# ElectronBoardMKII.net
KiCad netlist of a schematic drawn in EAGLE
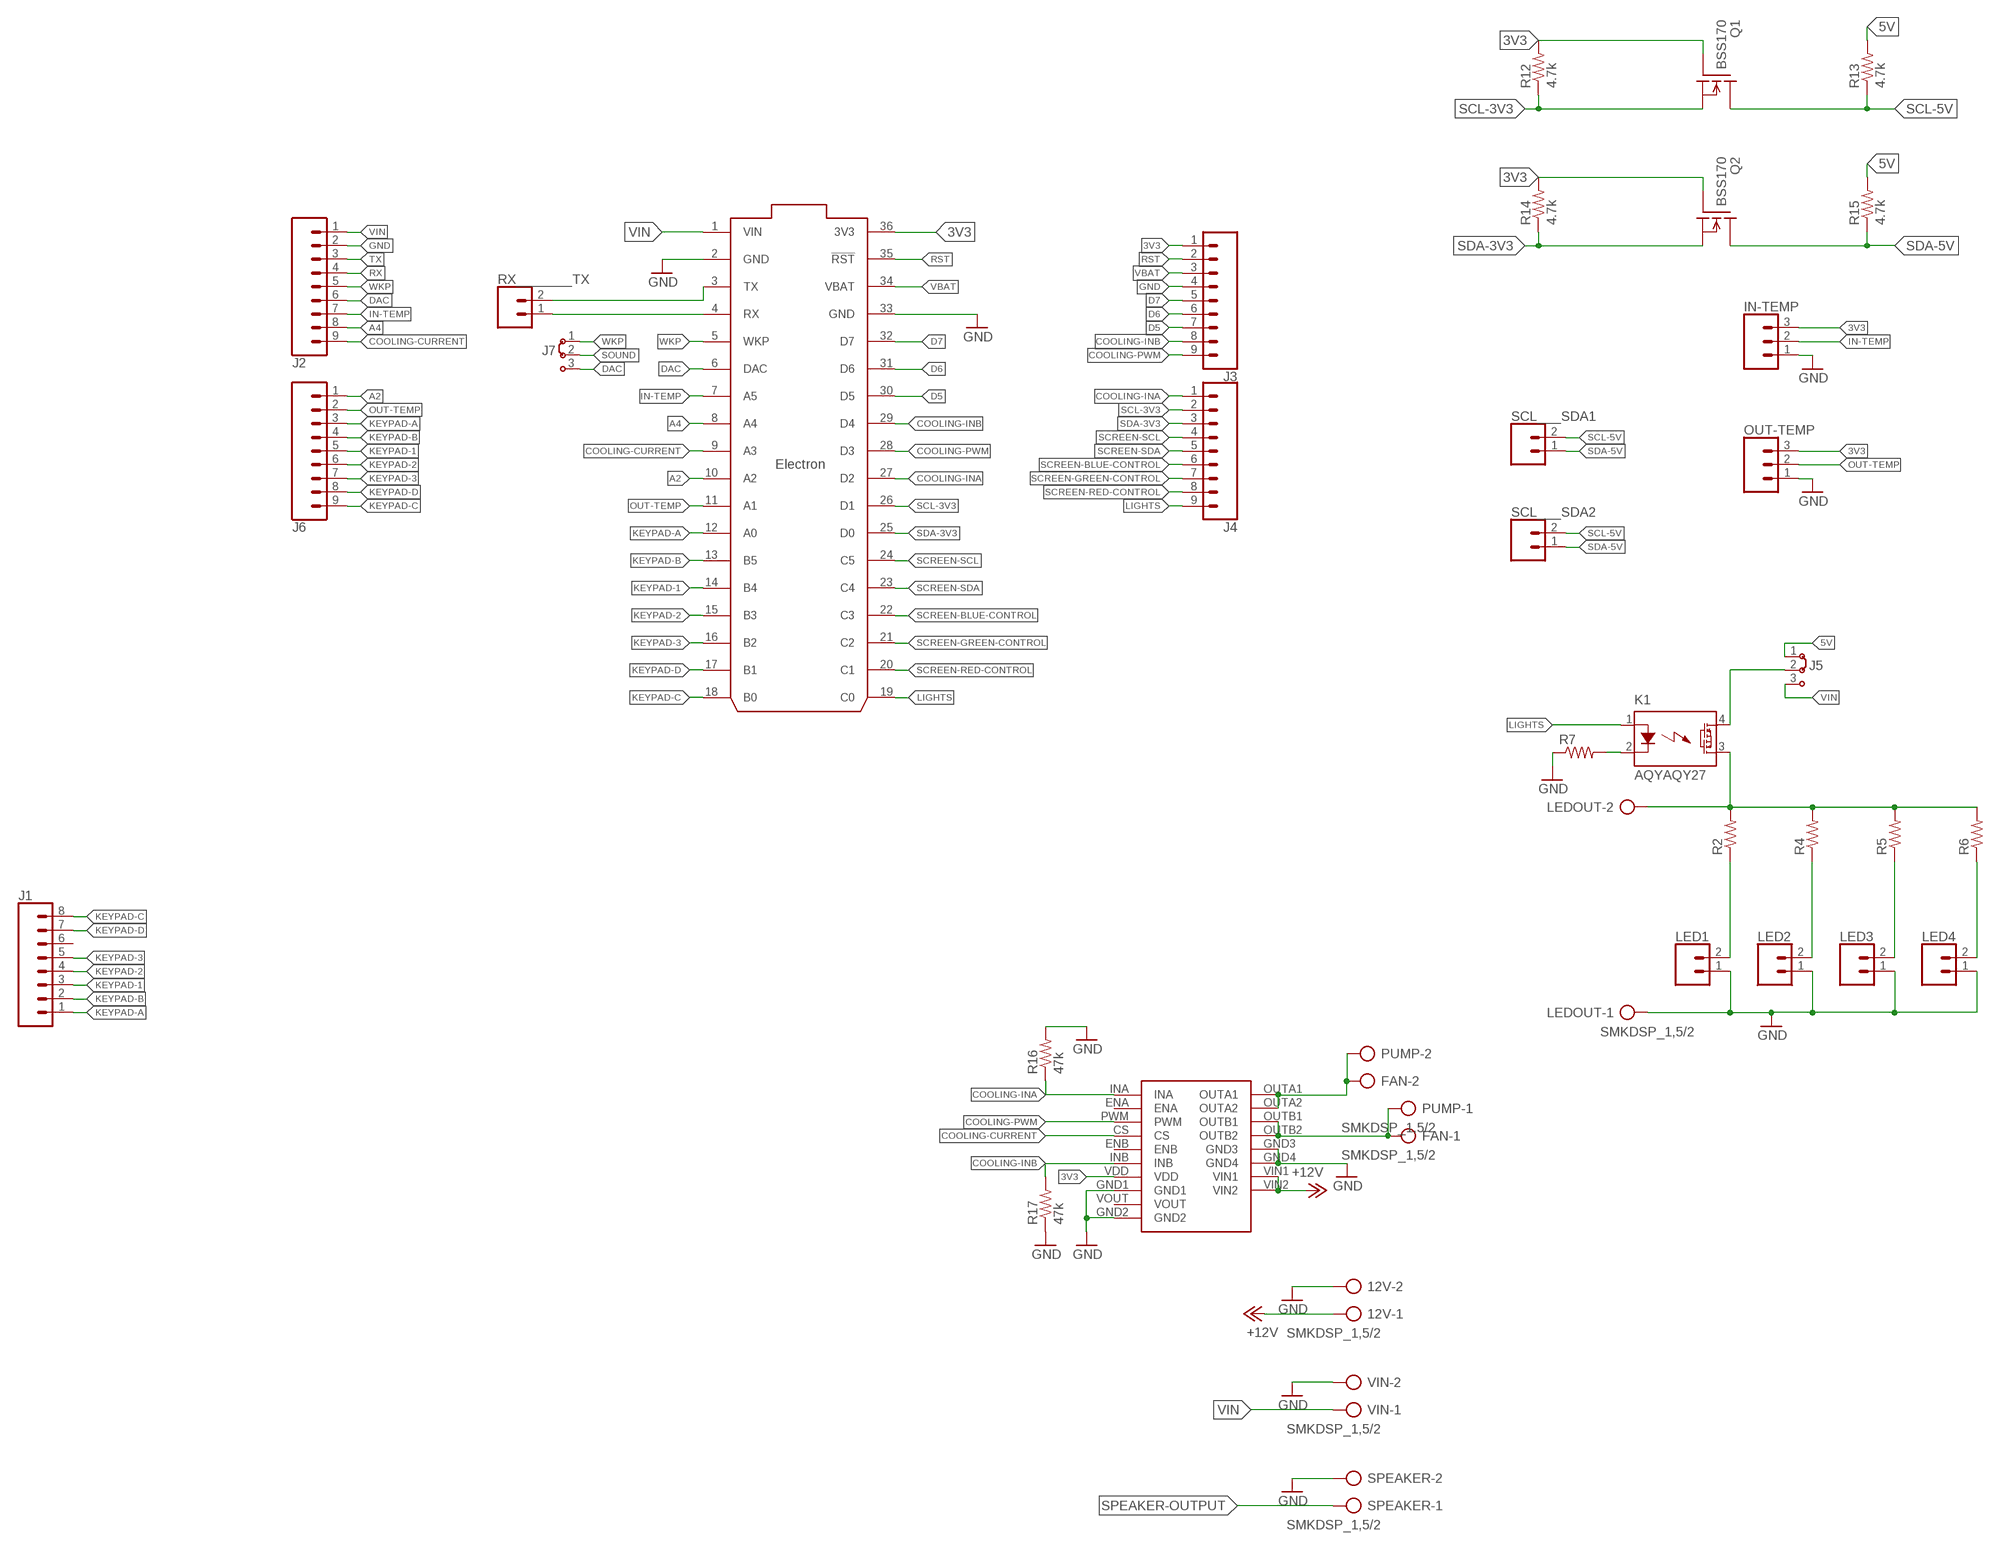
[diagram p0: schematic, sheet 1, part 1 of 2]
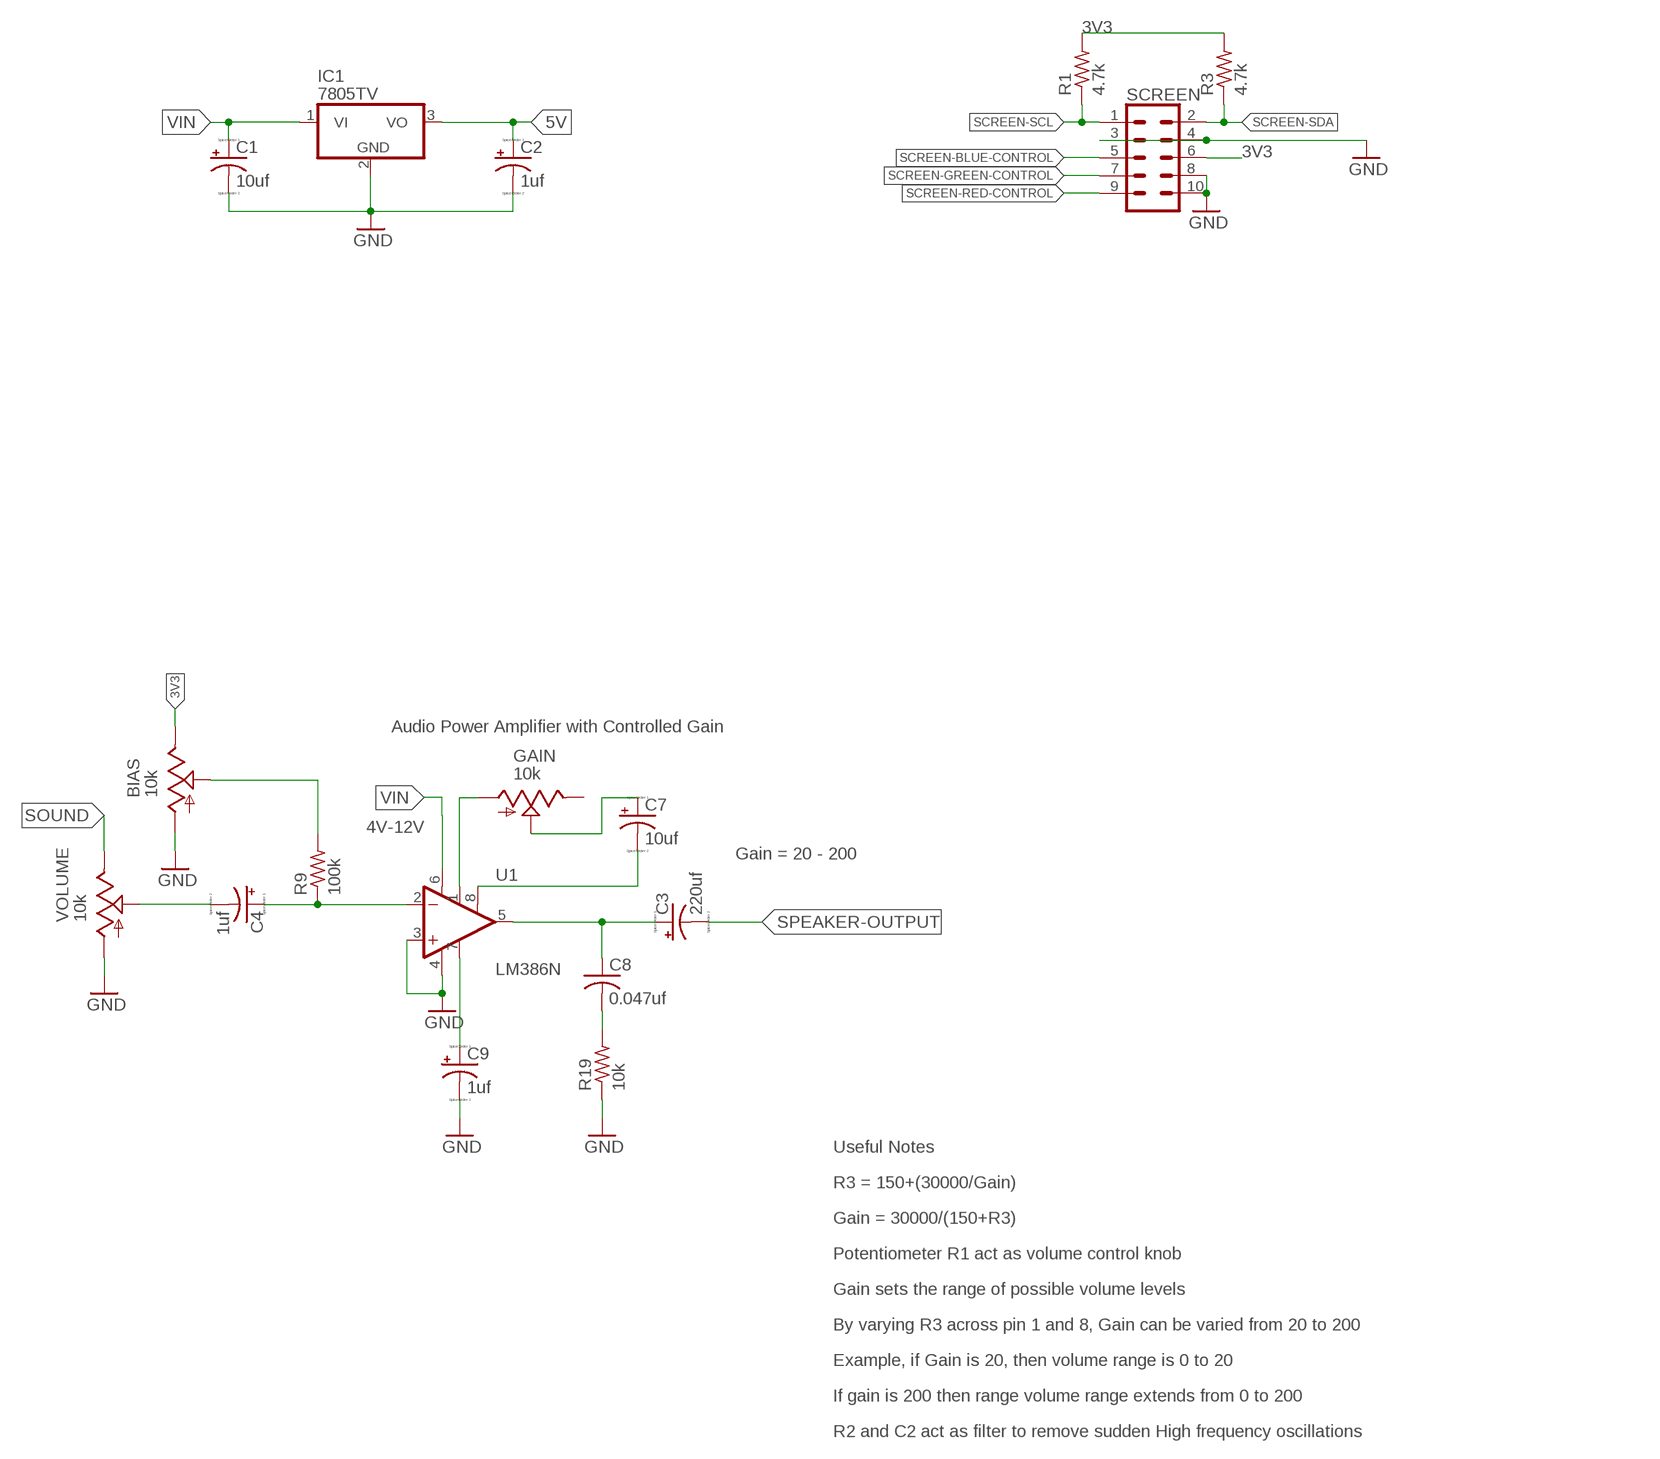
[diagram p1: schematic, sheet 1, part 2 of 2]

(export (version "E")
  (design (tool "Eeschema 10.0.6"))
  (components
    (comp (ref "12V")
      (value "SMKDSP_1,5/2")
      (footprint "eagle-import:SMKDSP_1,5_2")
      (fields (field (name "MF") "FARNELL") (field (name "MPN") "1733570"))
      (libsource (lib "eagle-import") (part "SMKDSP_1,5/2"))
    )
    (comp (ref "BIAS")
      (value "10k")
      (footprint "eagle-import:CT6")
      (libsource (lib "eagle-import") (part "TRIM_US-CT6"))
    )
    (comp (ref "C1")
      (value "10uf")
      (footprint "eagle-import:E5-8,5")
      (libsource (lib "eagle-import") (part "CPOL-USE5-8.5"))
    )
    (comp (ref "C2")
      (value "1uf")
      (footprint "eagle-import:E5-8,5")
      (libsource (lib "eagle-import") (part "CPOL-USE5-8.5"))
    )
    (comp (ref "C3")
      (value "220uf")
      (footprint "eagle-import:E5-8,5")
      (libsource (lib "eagle-import") (part "CPOL-USE5-8.5"))
    )
    (comp (ref "C4")
      (value "1uf")
      (footprint "eagle-import:E5-8,5")
      (libsource (lib "eagle-import") (part "CPOL-USE5-8.5"))
    )
    (comp (ref "C7")
      (value "10uf")
      (footprint "eagle-import:E5-8,5")
      (libsource (lib "eagle-import") (part "CPOL-USE5-8.5"))
    )
    (comp (ref "C8")
      (value "0.047uf")
      (footprint "eagle-import:C050-035X075")
      (libsource (lib "eagle-import") (part "C-US050-035X075"))
    )
    (comp (ref "C9")
      (value "1uf")
      (footprint "eagle-import:E5-8,5")
      (libsource (lib "eagle-import") (part "CPOL-USE5-8.5"))
    )
    (comp (ref "FAN")
      (value "SMKDSP_1,5/2")
      (footprint "eagle-import:SMKDSP_1,5_2")
      (fields (field (name "MF") "FARNELL") (field (name "MPN") "1733570"))
      (libsource (lib "eagle-import") (part "SMKDSP_1,5/2"))
    )
    (comp (ref "GAIN")
      (value "10k")
      (footprint "eagle-import:CT6")
      (libsource (lib "eagle-import") (part "TRIM_US-CT6"))
    )
    (comp (ref "IC1")
      (value "7805TV")
      (footprint "eagle-import:TO220V")
      (libsource (lib "eagle-import") (part "78TV05"))
    )
    (comp (ref "IN-TEMP")
      (value "CONN_03LOCK_LONGPADS")
      (footprint "eagle-import:1X03_LOCK_LONGPADS")
      (libsource (lib "eagle-import") (part "CONN_03LOCK_LONGPADS"))
    )
    (comp (ref "J1")
      (value "CONN_08LOCK_LONGPADS")
      (footprint "eagle-import:1X08_LOCK_LONGPADS")
      (libsource (lib "eagle-import") (part "CONN_08LOCK_LONGPADS"))
    )
    (comp (ref "J2")
      (value "CONN_09LOCK")
      (footprint "eagle-import:1X09_LOCK")
      (libsource (lib "eagle-import") (part "CONN_09LOCK"))
    )
    (comp (ref "J3")
      (value "CONN_09LOCK")
      (footprint "eagle-import:1X09_LOCK")
      (libsource (lib "eagle-import") (part "CONN_09LOCK"))
    )
    (comp (ref "J4")
      (value "CONN_09LOCK")
      (footprint "eagle-import:1X09_LOCK")
      (libsource (lib "eagle-import") (part "SparkFun-Connectors_513_CONN_09LOCK"))
    )
    (comp (ref "J5")
      (value "J2X2MM")
      (footprint "eagle-import:04C")
      (libsource (lib "eagle-import") (part "J2X2MM"))
    )
    (comp (ref "J6")
      (value "CONN_09LOCK")
      (footprint "eagle-import:1X09_LOCK")
      (libsource (lib "eagle-import") (part "CONN_09LOCK"))
    )
    (comp (ref "J7")
      (value "J2X2MM")
      (footprint "eagle-import:04C")
      (libsource (lib "eagle-import") (part "J2X2MM"))
    )
    (comp (ref "K1")
      (value "AQYAQY27")
      (footprint "eagle-import:AQY27")
      (libsource (lib "eagle-import") (part "AQYAQY27"))
    )
    (comp (ref "LED1")
      (value "CONN_02LOCK_LONGPADS")
      (footprint "eagle-import:1X02_LOCK_LONGPADS")
      (libsource (lib "eagle-import") (part "CONN_02LOCK_LONGPADS"))
    )
    (comp (ref "LED2")
      (value "CONN_02LOCK_LONGPADS")
      (footprint "eagle-import:1X02_LOCK_LONGPADS")
      (libsource (lib "eagle-import") (part "CONN_02LOCK_LONGPADS"))
    )
    (comp (ref "LED3")
      (value "CONN_02LOCK_LONGPADS")
      (footprint "eagle-import:1X02_LOCK_LONGPADS")
      (libsource (lib "eagle-import") (part "CONN_02LOCK_LONGPADS"))
    )
    (comp (ref "LED4")
      (value "CONN_02LOCK_LONGPADS")
      (footprint "eagle-import:1X02_LOCK_LONGPADS")
      (libsource (lib "eagle-import") (part "CONN_02LOCK_LONGPADS"))
    )
    (comp (ref "LEDOUT")
      (value "SMKDSP_1,5/2")
      (footprint "eagle-import:SMKDSP_1,5_2")
      (fields (field (name "MF") "FARNELL") (field (name "MPN") "1733570"))
      (libsource (lib "eagle-import") (part "SMKDSP_1,5/2"))
    )
    (comp (ref "OUT-TEMP")
      (value "CONN_03LOCK_LONGPADS")
      (footprint "eagle-import:1X03_LOCK_LONGPADS")
      (libsource (lib "eagle-import") (part "CONN_03LOCK_LONGPADS"))
    )
    (comp (ref "PUMP")
      (value "SMKDSP_1,5/2")
      (footprint "eagle-import:SMKDSP_1,5_2")
      (fields (field (name "MF") "FARNELL") (field (name "MPN") "1733570"))
      (libsource (lib "eagle-import") (part "SMKDSP_1,5/2"))
    )
    (comp (ref "Q1")
      (value "BSS170")
      (footprint "eagle-import:TO92")
      (libsource (lib "eagle-import") (part "BSS101"))
    )
    (comp (ref "Q2")
      (value "BSS170")
      (footprint "eagle-import:TO92")
      (libsource (lib "eagle-import") (part "BSS101"))
    )
    (comp (ref "R1")
      (value "4.7k")
      (footprint "eagle-import:0207_12")
      (libsource (lib "eagle-import") (part "resistor_348_R-US_0207/12"))
    )
    (comp (ref "R2")
      (value "R-US_0207/10")
      (footprint "eagle-import:0207_10")
      (libsource (lib "eagle-import") (part "R-US_0207/10"))
    )
    (comp (ref "R3")
      (value "4.7k")
      (footprint "eagle-import:0207_12")
      (libsource (lib "eagle-import") (part "resistor_348_R-US_0207/12"))
    )
    (comp (ref "R4")
      (value "R-US_0207/10")
      (footprint "eagle-import:0207_10")
      (libsource (lib "eagle-import") (part "R-US_0207/10"))
    )
    (comp (ref "R5")
      (value "R-US_0207/10")
      (footprint "eagle-import:0207_10")
      (libsource (lib "eagle-import") (part "R-US_0207/10"))
    )
    (comp (ref "R6")
      (value "R-US_0207/10")
      (footprint "eagle-import:0207_10")
      (libsource (lib "eagle-import") (part "R-US_0207/10"))
    )
    (comp (ref "R7")
      (value "R-US_0207/10")
      (footprint "eagle-import:0207_10")
      (libsource (lib "eagle-import") (part "R-US_0207/10"))
    )
    (comp (ref "R9")
      (value "100k")
      (footprint "eagle-import:0207_5V")
      (libsource (lib "eagle-import") (part "resistor_348_R-US_0207/5V"))
    )
    (comp (ref "R12")
      (value "4.7k")
      (footprint "eagle-import:0207_12")
      (libsource (lib "eagle-import") (part "resistor_348_R-US_0207/12"))
    )
    (comp (ref "R13")
      (value "4.7k")
      (footprint "eagle-import:0207_12")
      (libsource (lib "eagle-import") (part "resistor_348_R-US_0207/12"))
    )
    (comp (ref "R14")
      (value "4.7k")
      (footprint "eagle-import:0207_12")
      (libsource (lib "eagle-import") (part "resistor_348_R-US_0207/12"))
    )
    (comp (ref "R15")
      (value "4.7k")
      (footprint "eagle-import:0207_12")
      (libsource (lib "eagle-import") (part "resistor_348_R-US_0207/12"))
    )
    (comp (ref "R16")
      (value "47k")
      (footprint "eagle-import:0207_12")
      (libsource (lib "eagle-import") (part "resistor_348_R-US_0207/12"))
    )
    (comp (ref "R17")
      (value "47k")
      (footprint "eagle-import:0207_12")
      (libsource (lib "eagle-import") (part "resistor_348_R-US_0207/12"))
    )
    (comp (ref "R19")
      (value "10k")
      (footprint "eagle-import:0207_12")
      (libsource (lib "eagle-import") (part "resistor_348_R-US_0207/12"))
    )
    (comp (ref "RX_______TX")
      (value "CONN_02LOCK_LONGPADS")
      (footprint "eagle-import:1X02_LOCK_LONGPADS")
      (libsource (lib "eagle-import") (part "CONN_02LOCK_LONGPADS"))
    )
    (comp (ref "SCL___SDA1")
      (value "CONN_02LOCK_LONGPADS")
      (footprint "eagle-import:1X02_LOCK_LONGPADS")
      (libsource (lib "eagle-import") (part "CONN_02LOCK_LONGPADS"))
    )
    (comp (ref "SCL___SDA2")
      (value "CONN_02LOCK_LONGPADS")
      (footprint "eagle-import:1X02_LOCK_LONGPADS")
      (libsource (lib "eagle-import") (part "CONN_02LOCK_LONGPADS"))
    )
    (comp (ref "SCREEN")
      (value "CONN_05X2SHD")
      (footprint "eagle-import:2X5-SHROUDED")
      (libsource (lib "eagle-import") (part "CONN_05X2SHD"))
    )
    (comp (ref "SPEAKER")
      (value "SMKDSP_1,5/2")
      (footprint "eagle-import:SMKDSP_1,5_2")
      (fields (field (name "MF") "FARNELL") (field (name "MPN") "1733570"))
      (libsource (lib "eagle-import") (part "SMKDSP_1,5/2"))
    )
    (comp (ref "U$1")
      (value "ELECTRON_WITH_HEADERS")
      (footprint "eagle-import:ELECTRON")
      (libsource (lib "eagle-import") (part "ELECTRON_WITH_HEADERS"))
    )
    (comp (ref "U$2")
      (value "VNH5019VNH5019BOARD")
      (footprint "eagle-import:DIP3302W60P254L2400H500Q20B")
      (libsource (lib "eagle-import") (part "VNH5019VNH5019BOARD"))
    )
    (comp (ref "U1")
      (value "LM386N")
      (footprint "eagle-import:DIP08")
      (libsource (lib "eagle-import") (part "LM386"))
    )
    (comp (ref "VIN")
      (value "SMKDSP_1,5/2")
      (footprint "eagle-import:SMKDSP_1,5_2")
      (fields (field (name "MF") "FARNELL") (field (name "MPN") "1733570"))
      (libsource (lib "eagle-import") (part "SMKDSP_1,5/2"))
    )
    (comp (ref "VOLUME")
      (value "10k")
      (footprint "eagle-import:CT6")
      (libsource (lib "eagle-import") (part "TRIM_US-CT6"))
    )
  )
  (nets
    (net (code "1") (name "+12V") (class "Default")
      (node (ref "12V") (pin "1") (pinfunction "KL_1") (pintype "passive"))
      (node (ref "U$2") (pin "VIN1") (pinfunction "VIN1_VIN1") (pintype "bidirectional"))
      (node (ref "U$2") (pin "VIN2") (pinfunction "VIN2_VIN2") (pintype "bidirectional"))
    )
    (net (code "2") (name "3V3") (class "Default")
      (node (ref "BIAS") (pin "E") (pinfunction "E_E") (pintype "passive"))
      (node (ref "IN-TEMP") (pin "3") (pinfunction "3_3") (pintype "passive"))
      (node (ref "J3") (pin "1") (pinfunction "1_1") (pintype "passive"))
      (node (ref "OUT-TEMP") (pin "3") (pinfunction "3_3") (pintype "passive"))
      (node (ref "Q1") (pin "2") (pinfunction "G_2") (pintype "passive"))
      (node (ref "Q2") (pin "2") (pinfunction "G_2") (pintype "passive"))
      (node (ref "R1") (pin "2") (pinfunction "2_2") (pintype "passive"))
      (node (ref "R12") (pin "2") (pinfunction "2_2") (pintype "passive"))
      (node (ref "R14") (pin "2") (pinfunction "2_2") (pintype "passive"))
      (node (ref "R3") (pin "2") (pinfunction "2_2") (pintype "passive"))
      (node (ref "SCREEN") (pin "6") (pinfunction "6_6") (pintype "passive"))
      (node (ref "U$1") (pin "36") (pinfunction "3V3_36") (pintype "power_in"))
      (node (ref "U$2") (pin "VDD") (pinfunction "VDD_VDD") (pintype "bidirectional"))
    )
    (net (code "3") (name "5V") (class "Default")
      (node (ref "C2") (pin "+") (pinfunction "+_+") (pintype "passive"))
      (node (ref "IC1") (pin "3") (pinfunction "VO_3") (pintype "passive"))
      (node (ref "J5") (pin "1") (pinfunction "1_1") (pintype "passive"))
      (node (ref "R13") (pin "2") (pinfunction "2_2") (pintype "passive"))
      (node (ref "R15") (pin "2") (pinfunction "2_2") (pintype "passive"))
    )
    (net (code "4") (name "A2") (class "Default")
      (node (ref "J6") (pin "1") (pinfunction "1_1") (pintype "passive"))
      (node (ref "U$1") (pin "10") (pinfunction "A2_10") (pintype "bidirectional"))
    )
    (net (code "5") (name "A4") (class "Default")
      (node (ref "J2") (pin "8") (pinfunction "8_8") (pintype "passive"))
      (node (ref "U$1") (pin "8") (pinfunction "A4_8") (pintype "bidirectional"))
    )
    (net (code "6") (name "COOLING-CURRENT") (class "Default")
      (node (ref "J2") (pin "9") (pinfunction "9_9") (pintype "passive"))
      (node (ref "U$1") (pin "9") (pinfunction "A3_9") (pintype "bidirectional"))
      (node (ref "U$2") (pin "CS") (pinfunction "CS_CS") (pintype "bidirectional"))
    )
    (net (code "7") (name "COOLING-INA") (class "Default")
      (node (ref "J4") (pin "1") (pinfunction "1_1") (pintype "passive"))
      (node (ref "R16") (pin "1") (pinfunction "1_1") (pintype "passive"))
      (node (ref "U$1") (pin "27") (pinfunction "D2_27") (pintype "bidirectional"))
      (node (ref "U$2") (pin "INA") (pinfunction "INA_INA") (pintype "bidirectional"))
    )
    (net (code "8") (name "COOLING-INB") (class "Default")
      (node (ref "J3") (pin "8") (pinfunction "8_8") (pintype "passive"))
      (node (ref "R17") (pin "2") (pinfunction "2_2") (pintype "passive"))
      (node (ref "U$1") (pin "29") (pinfunction "D4_29") (pintype "bidirectional"))
      (node (ref "U$2") (pin "INB") (pinfunction "INB_INB") (pintype "bidirectional"))
    )
    (net (code "9") (name "COOLING-PWM") (class "Default")
      (node (ref "J3") (pin "9") (pinfunction "9_9") (pintype "passive"))
      (node (ref "U$1") (pin "28") (pinfunction "D3_28") (pintype "bidirectional"))
      (node (ref "U$2") (pin "PWM") (pinfunction "PWM_PWM") (pintype "bidirectional"))
    )
    (net (code "10") (name "D5") (class "Default")
      (node (ref "J3") (pin "7") (pinfunction "7_7") (pintype "passive"))
      (node (ref "U$1") (pin "30") (pinfunction "D5_30") (pintype "bidirectional"))
    )
    (net (code "11") (name "D6") (class "Default")
      (node (ref "J3") (pin "6") (pinfunction "6_6") (pintype "passive"))
      (node (ref "U$1") (pin "31") (pinfunction "D6_31") (pintype "bidirectional"))
    )
    (net (code "12") (name "D7") (class "Default")
      (node (ref "J3") (pin "5") (pinfunction "5_5") (pintype "passive"))
      (node (ref "U$1") (pin "32") (pinfunction "D7_32") (pintype "bidirectional"))
    )
    (net (code "13") (name "DAC") (class "Default")
      (node (ref "J2") (pin "6") (pinfunction "6_6") (pintype "passive"))
      (node (ref "J7") (pin "3") (pinfunction "3_3") (pintype "passive"))
      (node (ref "U$1") (pin "6") (pinfunction "DAC_6") (pintype "bidirectional"))
    )
    (net (code "14") (name "GND") (class "Default")
      (node (ref "12V") (pin "2") (pinfunction "KL_2") (pintype "passive"))
      (node (ref "BIAS") (pin "A") (pinfunction "A_A") (pintype "passive"))
      (node (ref "C1") (pin "-") (pinfunction "-_-") (pintype "passive"))
      (node (ref "C2") (pin "-") (pinfunction "-_-") (pintype "passive"))
      (node (ref "C9") (pin "-") (pinfunction "-_-") (pintype "passive"))
      (node (ref "IC1") (pin "2") (pinfunction "GND_2") (pintype "passive"))
      (node (ref "IN-TEMP") (pin "1") (pinfunction "1_1") (pintype "passive"))
      (node (ref "J2") (pin "2") (pinfunction "2_2") (pintype "passive"))
      (node (ref "J3") (pin "4") (pinfunction "4_4") (pintype "passive"))
      (node (ref "LED1") (pin "1") (pinfunction "1_1") (pintype "passive"))
      (node (ref "LED2") (pin "1") (pinfunction "1_1") (pintype "passive"))
      (node (ref "LED3") (pin "1") (pinfunction "1_1") (pintype "passive"))
      (node (ref "LED4") (pin "1") (pinfunction "1_1") (pintype "passive"))
      (node (ref "LEDOUT") (pin "1") (pinfunction "KL_1") (pintype "passive"))
      (node (ref "OUT-TEMP") (pin "1") (pinfunction "1_1") (pintype "passive"))
      (node (ref "R16") (pin "2") (pinfunction "2_2") (pintype "passive"))
      (node (ref "R17") (pin "1") (pinfunction "1_1") (pintype "passive"))
      (node (ref "R19") (pin "1") (pinfunction "1_1") (pintype "passive"))
      (node (ref "R7") (pin "1") (pinfunction "1_1") (pintype "passive"))
      (node (ref "SCREEN") (pin "10") (pinfunction "10_10") (pintype "passive"))
      (node (ref "SCREEN") (pin "3") (pinfunction "3_3") (pintype "passive"))
      (node (ref "SCREEN") (pin "4") (pinfunction "4_4") (pintype "passive"))
      (node (ref "SCREEN") (pin "8") (pinfunction "8_8") (pintype "passive"))
      (node (ref "SPEAKER") (pin "2") (pinfunction "KL_2") (pintype "passive"))
      (node (ref "U$1") (pin "2") (pinfunction "GND_2") (pintype "power_in"))
      (node (ref "U$1") (pin "33") (pinfunction "GND_33") (pintype "power_in"))
      (node (ref "U$2") (pin "GND1") (pinfunction "GND1_GND1") (pintype "bidirectional"))
      (node (ref "U$2") (pin "GND2") (pinfunction "GND2_GND2") (pintype "bidirectional"))
      (node (ref "U$2") (pin "GND3") (pinfunction "GND3_GND3") (pintype "bidirectional"))
      (node (ref "U$2") (pin "GND4") (pinfunction "GND4_GND4") (pintype "bidirectional"))
      (node (ref "U1") (pin "3") (pinfunction "+IN_3") (pintype "input"))
      (node (ref "U1") (pin "4") (pinfunction "V-_4") (pintype "power_in"))
      (node (ref "VIN") (pin "2") (pinfunction "KL_2") (pintype "passive"))
      (node (ref "VOLUME") (pin "A") (pinfunction "A_A") (pintype "passive"))
    )
    (net (code "15") (name "IN-TEMP") (class "Default")
      (node (ref "IN-TEMP") (pin "2") (pinfunction "2_2") (pintype "passive"))
      (node (ref "J2") (pin "7") (pinfunction "7_7") (pintype "passive"))
      (node (ref "U$1") (pin "7") (pinfunction "A5_7") (pintype "bidirectional"))
    )
    (net (code "16") (name "KEYPAD-1") (class "Default")
      (node (ref "J1") (pin "3") (pinfunction "3_3") (pintype "passive"))
      (node (ref "J6") (pin "5") (pinfunction "5_5") (pintype "passive"))
      (node (ref "U$1") (pin "14") (pinfunction "B4_14") (pintype "bidirectional"))
    )
    (net (code "17") (name "KEYPAD-2") (class "Default")
      (node (ref "J1") (pin "4") (pinfunction "4_4") (pintype "passive"))
      (node (ref "J6") (pin "6") (pinfunction "6_6") (pintype "passive"))
      (node (ref "U$1") (pin "15") (pinfunction "B3_15") (pintype "bidirectional"))
    )
    (net (code "18") (name "KEYPAD-3") (class "Default")
      (node (ref "J1") (pin "5") (pinfunction "5_5") (pintype "passive"))
      (node (ref "J6") (pin "7") (pinfunction "7_7") (pintype "passive"))
      (node (ref "U$1") (pin "16") (pinfunction "B2_16") (pintype "bidirectional"))
    )
    (net (code "19") (name "KEYPAD-A") (class "Default")
      (node (ref "J1") (pin "1") (pinfunction "1_1") (pintype "passive"))
      (node (ref "J6") (pin "3") (pinfunction "3_3") (pintype "passive"))
      (node (ref "U$1") (pin "12") (pinfunction "A0_12") (pintype "bidirectional"))
    )
    (net (code "20") (name "KEYPAD-B") (class "Default")
      (node (ref "J1") (pin "2") (pinfunction "2_2") (pintype "passive"))
      (node (ref "J6") (pin "4") (pinfunction "4_4") (pintype "passive"))
      (node (ref "U$1") (pin "13") (pinfunction "B5_13") (pintype "bidirectional"))
    )
    (net (code "21") (name "KEYPAD-C") (class "Default")
      (node (ref "J1") (pin "8") (pinfunction "8_8") (pintype "passive"))
      (node (ref "J6") (pin "9") (pinfunction "9_9") (pintype "passive"))
      (node (ref "U$1") (pin "18") (pinfunction "B0_18") (pintype "bidirectional"))
    )
    (net (code "22") (name "KEYPAD-D") (class "Default")
      (node (ref "J1") (pin "7") (pinfunction "7_7") (pintype "passive"))
      (node (ref "J6") (pin "8") (pinfunction "8_8") (pintype "passive"))
      (node (ref "U$1") (pin "17") (pinfunction "B1_17") (pintype "bidirectional"))
    )
    (net (code "23") (name "LIGHTS") (class "Default")
      (node (ref "J4") (pin "9") (pinfunction "9_9") (pintype "passive"))
      (node (ref "K1") (pin "1") (pinfunction "A_1") (pintype "passive"))
      (node (ref "U$1") (pin "19") (pinfunction "C0_19") (pintype "bidirectional"))
    )
    (net (code "24") (name "Net-(BIAS-PadS)") (class "Default")
      (node (ref "BIAS") (pin "S") (pinfunction "S_S") (pintype "passive"))
      (node (ref "R9") (pin "2") (pinfunction "2_2") (pintype "passive"))
    )
    (net (code "25") (name "Net-(C4-Pad-)") (class "Default")
      (node (ref "C4") (pin "-") (pinfunction "-_-") (pintype "passive"))
      (node (ref "VOLUME") (pin "S") (pinfunction "S_S") (pintype "passive"))
    )
    (net (code "26") (name "Net-(C7-Pad+)") (class "Default")
      (node (ref "C7") (pin "+") (pinfunction "+_+") (pintype "passive"))
      (node (ref "GAIN") (pin "S") (pinfunction "S_S") (pintype "passive"))
    )
    (net (code "27") (name "Net-(C7-Pad-)") (class "Default")
      (node (ref "C7") (pin "-") (pinfunction "-_-") (pintype "passive"))
      (node (ref "U1") (pin "8") (pinfunction "GAIN_8") (pintype "bidirectional"))
    )
    (net (code "28") (name "Net-(C8-Pad2)") (class "Default")
      (node (ref "C8") (pin "2") (pinfunction "2_2") (pintype "passive"))
      (node (ref "R19") (pin "2") (pinfunction "2_2") (pintype "passive"))
    )
    (net (code "29") (name "Net-(FANA-KL)") (class "Default")
      (node (ref "FAN") (pin "1") (pinfunction "KL_1") (pintype "passive"))
      (node (ref "PUMP") (pin "1") (pinfunction "KL_1") (pintype "passive"))
      (node (ref "U$2") (pin "OUTB1") (pinfunction "OUTB1_OUTB1") (pintype "bidirectional"))
      (node (ref "U$2") (pin "OUTB2") (pinfunction "OUTB2_OUTB2") (pintype "bidirectional"))
    )
    (net (code "30") (name "Net-(FANB-KL)") (class "Default")
      (node (ref "FAN") (pin "2") (pinfunction "KL_2") (pintype "passive"))
      (node (ref "PUMP") (pin "2") (pinfunction "KL_2") (pintype "passive"))
      (node (ref "U$2") (pin "OUTA1") (pinfunction "OUTA1_OUTA1") (pintype "bidirectional"))
      (node (ref "U$2") (pin "OUTA2") (pinfunction "OUTA2_OUTA2") (pintype "bidirectional"))
    )
    (net (code "31") (name "Net-(GAIN-PadA)") (class "Default")
      (node (ref "GAIN") (pin "A") (pinfunction "A_A") (pintype "passive"))
      (node (ref "U1") (pin "1") (pinfunction "GAIN_1") (pintype "bidirectional"))
    )
    (net (code "32") (name "Net-(K1-DS1)") (class "Default")
      (node (ref "J5") (pin "2") (pinfunction "2_2") (pintype "passive"))
      (node (ref "K1") (pin "4") (pinfunction "DS1_4") (pintype "passive"))
    )
    (net (code "33") (name "Net-(K1-DS2)") (class "Default")
      (node (ref "K1") (pin "3") (pinfunction "DS2_3") (pintype "passive"))
      (node (ref "LEDOUT") (pin "2") (pinfunction "KL_2") (pintype "passive"))
      (node (ref "R2") (pin "2") (pinfunction "2_2") (pintype "passive"))
      (node (ref "R4") (pin "2") (pinfunction "2_2") (pintype "passive"))
      (node (ref "R5") (pin "2") (pinfunction "2_2") (pintype "passive"))
      (node (ref "R6") (pin "2") (pinfunction "2_2") (pintype "passive"))
    )
    (net (code "34") (name "Net-(K1-K)") (class "Default")
      (node (ref "K1") (pin "2") (pinfunction "K_2") (pintype "passive"))
      (node (ref "R7") (pin "2") (pinfunction "2_2") (pintype "passive"))
    )
    (net (code "35") (name "Net-(LED1-Pad2)") (class "Default")
      (node (ref "LED1") (pin "2") (pinfunction "2_2") (pintype "passive"))
      (node (ref "R2") (pin "1") (pinfunction "1_1") (pintype "passive"))
    )
    (net (code "36") (name "Net-(LED2-Pad2)") (class "Default")
      (node (ref "LED2") (pin "2") (pinfunction "2_2") (pintype "passive"))
      (node (ref "R4") (pin "1") (pinfunction "1_1") (pintype "passive"))
    )
    (net (code "37") (name "Net-(LED3-Pad2)") (class "Default")
      (node (ref "LED3") (pin "2") (pinfunction "2_2") (pintype "passive"))
      (node (ref "R5") (pin "1") (pinfunction "1_1") (pintype "passive"))
    )
    (net (code "38") (name "Net-(LED4-Pad2)") (class "Default")
      (node (ref "LED4") (pin "2") (pinfunction "2_2") (pintype "passive"))
      (node (ref "R6") (pin "1") (pinfunction "1_1") (pintype "passive"))
    )
    (net (code "39") (name "Net-(U1--IN)") (class "Default")
      (node (ref "C4") (pin "+") (pinfunction "+_+") (pintype "passive"))
      (node (ref "R9") (pin "1") (pinfunction "1_1") (pintype "passive"))
      (node (ref "U1") (pin "2") (pinfunction "-IN_2") (pintype "input"))
    )
    (net (code "40") (name "Net-(U1-BP)") (class "Default")
      (node (ref "C9") (pin "+") (pinfunction "+_+") (pintype "passive"))
      (node (ref "U1") (pin "7") (pinfunction "BP_7") (pintype "bidirectional"))
    )
    (net (code "41") (name "Net-(U1-OUT)") (class "Default")
      (node (ref "C3") (pin "+") (pinfunction "+_+") (pintype "passive"))
      (node (ref "C8") (pin "1") (pinfunction "1_1") (pintype "passive"))
      (node (ref "U1") (pin "5") (pinfunction "OUT_5") (pintype "output"))
    )
    (net (code "42") (name "OUT-TEMP") (class "Default")
      (node (ref "J6") (pin "2") (pinfunction "2_2") (pintype "passive"))
      (node (ref "OUT-TEMP") (pin "2") (pinfunction "2_2") (pintype "passive"))
      (node (ref "U$1") (pin "11") (pinfunction "A1_11") (pintype "bidirectional"))
    )
    (net (code "43") (name "RST") (class "Default")
      (node (ref "J3") (pin "2") (pinfunction "2_2") (pintype "passive"))
      (node (ref "U$1") (pin "35") (pinfunction "~{RST}_35") (pintype "bidirectional"))
    )
    (net (code "44") (name "RX") (class "Default")
      (node (ref "J2") (pin "4") (pinfunction "4_4") (pintype "passive"))
      (node (ref "RX_______TX") (pin "1") (pinfunction "1_1") (pintype "passive"))
      (node (ref "U$1") (pin "4") (pinfunction "RX_4") (pintype "bidirectional"))
    )
    (net (code "45") (name "SCL-3V3") (class "Default")
      (node (ref "J4") (pin "2") (pinfunction "2_2") (pintype "passive"))
      (node (ref "Q1") (pin "1") (pinfunction "S_1") (pintype "passive"))
      (node (ref "R12") (pin "1") (pinfunction "1_1") (pintype "passive"))
      (node (ref "U$1") (pin "26") (pinfunction "D1_26") (pintype "bidirectional"))
    )
    (net (code "46") (name "SCL-5V") (class "Default")
      (node (ref "Q1") (pin "3") (pinfunction "D_3") (pintype "passive"))
      (node (ref "R13") (pin "1") (pinfunction "1_1") (pintype "passive"))
      (node (ref "SCL___SDA1") (pin "2") (pinfunction "2_2") (pintype "passive"))
      (node (ref "SCL___SDA2") (pin "2") (pinfunction "2_2") (pintype "passive"))
    )
    (net (code "47") (name "SCREEN-BLUE-CONTROL") (class "Default")
      (node (ref "J4") (pin "6") (pinfunction "6_6") (pintype "passive"))
      (node (ref "SCREEN") (pin "5") (pinfunction "5_5") (pintype "passive"))
      (node (ref "U$1") (pin "22") (pinfunction "C3_22") (pintype "bidirectional"))
    )
    (net (code "48") (name "SCREEN-GREEN-CONTROL") (class "Default")
      (node (ref "J4") (pin "7") (pinfunction "7_7") (pintype "passive"))
      (node (ref "SCREEN") (pin "7") (pinfunction "7_7") (pintype "passive"))
      (node (ref "U$1") (pin "21") (pinfunction "C2_21") (pintype "bidirectional"))
    )
    (net (code "49") (name "SCREEN-RED-CONTROL") (class "Default")
      (node (ref "J4") (pin "8") (pinfunction "8_8") (pintype "passive"))
      (node (ref "SCREEN") (pin "9") (pinfunction "9_9") (pintype "passive"))
      (node (ref "U$1") (pin "20") (pinfunction "C1_20") (pintype "bidirectional"))
    )
    (net (code "50") (name "SCREEN-SCL") (class "Default")
      (node (ref "J4") (pin "4") (pinfunction "4_4") (pintype "passive"))
      (node (ref "R1") (pin "1") (pinfunction "1_1") (pintype "passive"))
      (node (ref "SCREEN") (pin "1") (pinfunction "1_1") (pintype "passive"))
      (node (ref "U$1") (pin "24") (pinfunction "C5_24") (pintype "bidirectional"))
    )
    (net (code "51") (name "SCREEN-SDA") (class "Default")
      (node (ref "J4") (pin "5") (pinfunction "5_5") (pintype "passive"))
      (node (ref "R3") (pin "1") (pinfunction "1_1") (pintype "passive"))
      (node (ref "SCREEN") (pin "2") (pinfunction "2_2") (pintype "passive"))
      (node (ref "U$1") (pin "23") (pinfunction "C4_23") (pintype "bidirectional"))
    )
    (net (code "52") (name "SDA-3V3") (class "Default")
      (node (ref "J4") (pin "3") (pinfunction "3_3") (pintype "passive"))
      (node (ref "Q2") (pin "1") (pinfunction "S_1") (pintype "passive"))
      (node (ref "R14") (pin "1") (pinfunction "1_1") (pintype "passive"))
      (node (ref "U$1") (pin "25") (pinfunction "D0_25") (pintype "bidirectional"))
    )
    (net (code "53") (name "SDA-5V") (class "Default")
      (node (ref "Q2") (pin "3") (pinfunction "D_3") (pintype "passive"))
      (node (ref "R15") (pin "1") (pinfunction "1_1") (pintype "passive"))
      (node (ref "SCL___SDA1") (pin "1") (pinfunction "1_1") (pintype "passive"))
      (node (ref "SCL___SDA2") (pin "1") (pinfunction "1_1") (pintype "passive"))
    )
    (net (code "54") (name "SOUND") (class "Default")
      (node (ref "J7") (pin "2") (pinfunction "2_2") (pintype "passive"))
      (node (ref "VOLUME") (pin "E") (pinfunction "E_E") (pintype "passive"))
    )
    (net (code "55") (name "SPEAKER-OUTPUT") (class "Default")
      (node (ref "C3") (pin "-") (pinfunction "-_-") (pintype "passive"))
      (node (ref "SPEAKER") (pin "1") (pinfunction "KL_1") (pintype "passive"))
    )
    (net (code "56") (name "TX") (class "Default")
      (node (ref "J2") (pin "3") (pinfunction "3_3") (pintype "passive"))
      (node (ref "RX_______TX") (pin "2") (pinfunction "2_2") (pintype "passive"))
      (node (ref "U$1") (pin "3") (pinfunction "TX_3") (pintype "bidirectional"))
    )
    (net (code "57") (name "VBAT") (class "Default")
      (node (ref "J3") (pin "3") (pinfunction "3_3") (pintype "passive"))
      (node (ref "U$1") (pin "34") (pinfunction "VBAT_34") (pintype "power_in"))
    )
    (net (code "58") (name "VIN") (class "Default")
      (node (ref "C1") (pin "+") (pinfunction "+_+") (pintype "passive"))
      (node (ref "IC1") (pin "1") (pinfunction "VI_1") (pintype "input"))
      (node (ref "J2") (pin "1") (pinfunction "1_1") (pintype "passive"))
      (node (ref "J5") (pin "3") (pinfunction "3_3") (pintype "passive"))
      (node (ref "U$1") (pin "1") (pinfunction "VIN_1") (pintype "power_in"))
      (node (ref "U1") (pin "6") (pinfunction "V+_6") (pintype "power_in"))
      (node (ref "VIN") (pin "1") (pinfunction "KL_1") (pintype "passive"))
    )
    (net (code "59") (name "WKP") (class "Default")
      (node (ref "J2") (pin "5") (pinfunction "5_5") (pintype "passive"))
      (node (ref "J7") (pin "1") (pinfunction "1_1") (pintype "passive"))
      (node (ref "U$1") (pin "5") (pinfunction "WKP_5") (pintype "bidirectional"))
    )
    (net (code "60") (name "unconnected-(GAIN-PadE)") (class "Default")
      (node (ref "GAIN") (pin "E") (pinfunction "E_E") (pintype "passive"))
    )
    (net (code "61") (name "unconnected-(J1-Pad6)") (class "Default")
      (node (ref "J1") (pin "6") (pinfunction "6_6") (pintype "passive"))
    )
    (net (code "62") (name "unconnected-(U$2-PadENA)") (class "Default")
      (node (ref "U$2") (pin "ENA") (pinfunction "ENA_ENA") (pintype "bidirectional"))
    )
    (net (code "63") (name "unconnected-(U$2-PadENB)") (class "Default")
      (node (ref "U$2") (pin "ENB") (pinfunction "ENB_ENB") (pintype "bidirectional"))
    )
    (net (code "64") (name "unconnected-(U$2-PadVOUT)") (class "Default")
      (node (ref "U$2") (pin "VOUT") (pinfunction "VOUT_VOUT") (pintype "bidirectional"))
    )
  )
)
